# transponder.net
KiCad netlist of a schematic drawn in EAGLE
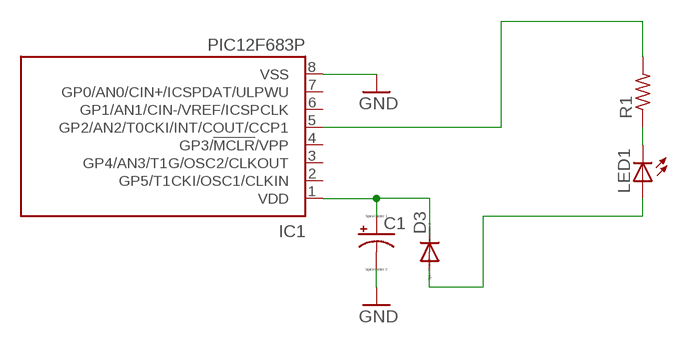
[diagram p0: schematic, sheet 1]

(export (version "E")
  (design (tool "Eeschema 10.0.6"))
  (components
    (comp (ref "C1")
      (value "CPOL-US153CLV-0505")
      (footprint "eagle-import:153CLV-0505")
      (libsource (lib "eagle-import") (part "CPOL-US153CLV-0505"))
    )
    (comp (ref "D3")
      (value "DIODE-DO-214AC")
      (footprint "eagle-import:DO-214AC")
      (libsource (lib "eagle-import") (part "DIODE-DO-214AC"))
    )
    (comp (ref "IC1")
      (value "PIC12F683P")
      (footprint "eagle-import:DIL8")
      (fields (field (name "MF") "MICROCHIP") (field (name "MPN") "PIC12F683-I/P"))
      (libsource (lib "eagle-import") (part "PIC12F683P"))
    )
    (comp (ref "LED1")
      (value "LED3MM")
      (footprint "eagle-import:LED3MM")
      (libsource (lib "eagle-import") (part "LED3MM"))
    )
    (comp (ref "R1")
      (value "R-US_M0805")
      (footprint "eagle-import:M0805")
      (libsource (lib "eagle-import") (part "R-US_M0805"))
    )
  )
  (nets
    (net (code "1") (name "GND") (class "Default")
      (node (ref "C1") (pin "-") (pinfunction "-_-") (pintype "passive"))
      (node (ref "IC1") (pin "8") (pinfunction "VSS_8") (pintype "power_in"))
    )
    (net (code "2") (name "Net-(D3-PadA)") (class "Default")
      (node (ref "D3") (pin "A") (pinfunction "A_A") (pintype "passive"))
      (node (ref "LED1") (pin "A") (pinfunction "A_A") (pintype "passive"))
    )
    (net (code "3") (name "Net-(IC1-GP2{slash}AN2{slash}T0CKI{slash}INT{slash}COUT{slash}CCP1)") (class "Default")
      (node (ref "IC1") (pin "5") (pinfunction "GP2/AN2/T0CKI/INT/COUT/CCP1_5") (pintype "bidirectional"))
      (node (ref "R1") (pin "2") (pinfunction "2_2") (pintype "passive"))
    )
    (net (code "4") (name "Net-(IC1-VDD)") (class "Default")
      (node (ref "C1") (pin "+") (pinfunction "+_+") (pintype "passive"))
      (node (ref "D3") (pin "C") (pinfunction "C_C") (pintype "passive"))
      (node (ref "IC1") (pin "1") (pinfunction "VDD_1") (pintype "power_in"))
    )
    (net (code "5") (name "Net-(LED1-C)") (class "Default")
      (node (ref "LED1") (pin "K") (pinfunction "C_K") (pintype "passive"))
      (node (ref "R1") (pin "1") (pinfunction "1_1") (pintype "passive"))
    )
    (net (code "6") (name "unconnected-(IC1-GP0{slash}AN0{slash}CIN+{slash}ICSPDAT{slash}ULPWU-Pad7)") (class "Default")
      (node (ref "IC1") (pin "7") (pinfunction "GP0/AN0/CIN+/ICSPDAT/ULPWU_7") (pintype "bidirectional"))
    )
    (net (code "7") (name "unconnected-(IC1-GP1{slash}AN1{slash}CIN-{slash}VREF{slash}ICSPCLK-Pad6)") (class "Default")
      (node (ref "IC1") (pin "6") (pinfunction "GP1/AN1/CIN-/VREF/ICSPCLK_6") (pintype "bidirectional"))
    )
    (net (code "8") (name "unconnected-(IC1-GP3{slash}~{MCLR}{slash}VPP-Pad4)") (class "Default")
      (node (ref "IC1") (pin "4") (pinfunction "GP3/~{MCLR}/VPP_4") (pintype "bidirectional"))
    )
    (net (code "9") (name "unconnected-(IC1-GP4{slash}AN3{slash}T1G{slash}OSC2{slash}CLKOUT-Pad3)") (class "Default")
      (node (ref "IC1") (pin "3") (pinfunction "GP4/AN3/T1G/OSC2/CLKOUT_3") (pintype "bidirectional"))
    )
    (net (code "10") (name "unconnected-(IC1-GP5{slash}T1CKI{slash}OSC1{slash}CLKIN-Pad2)") (class "Default")
      (node (ref "IC1") (pin "2") (pinfunction "GP5/T1CKI/OSC1/CLKIN_2") (pintype "bidirectional"))
    )
  )
)
